# nixie_without_colon.net
KiCad netlist of a schematic drawn in EAGLE
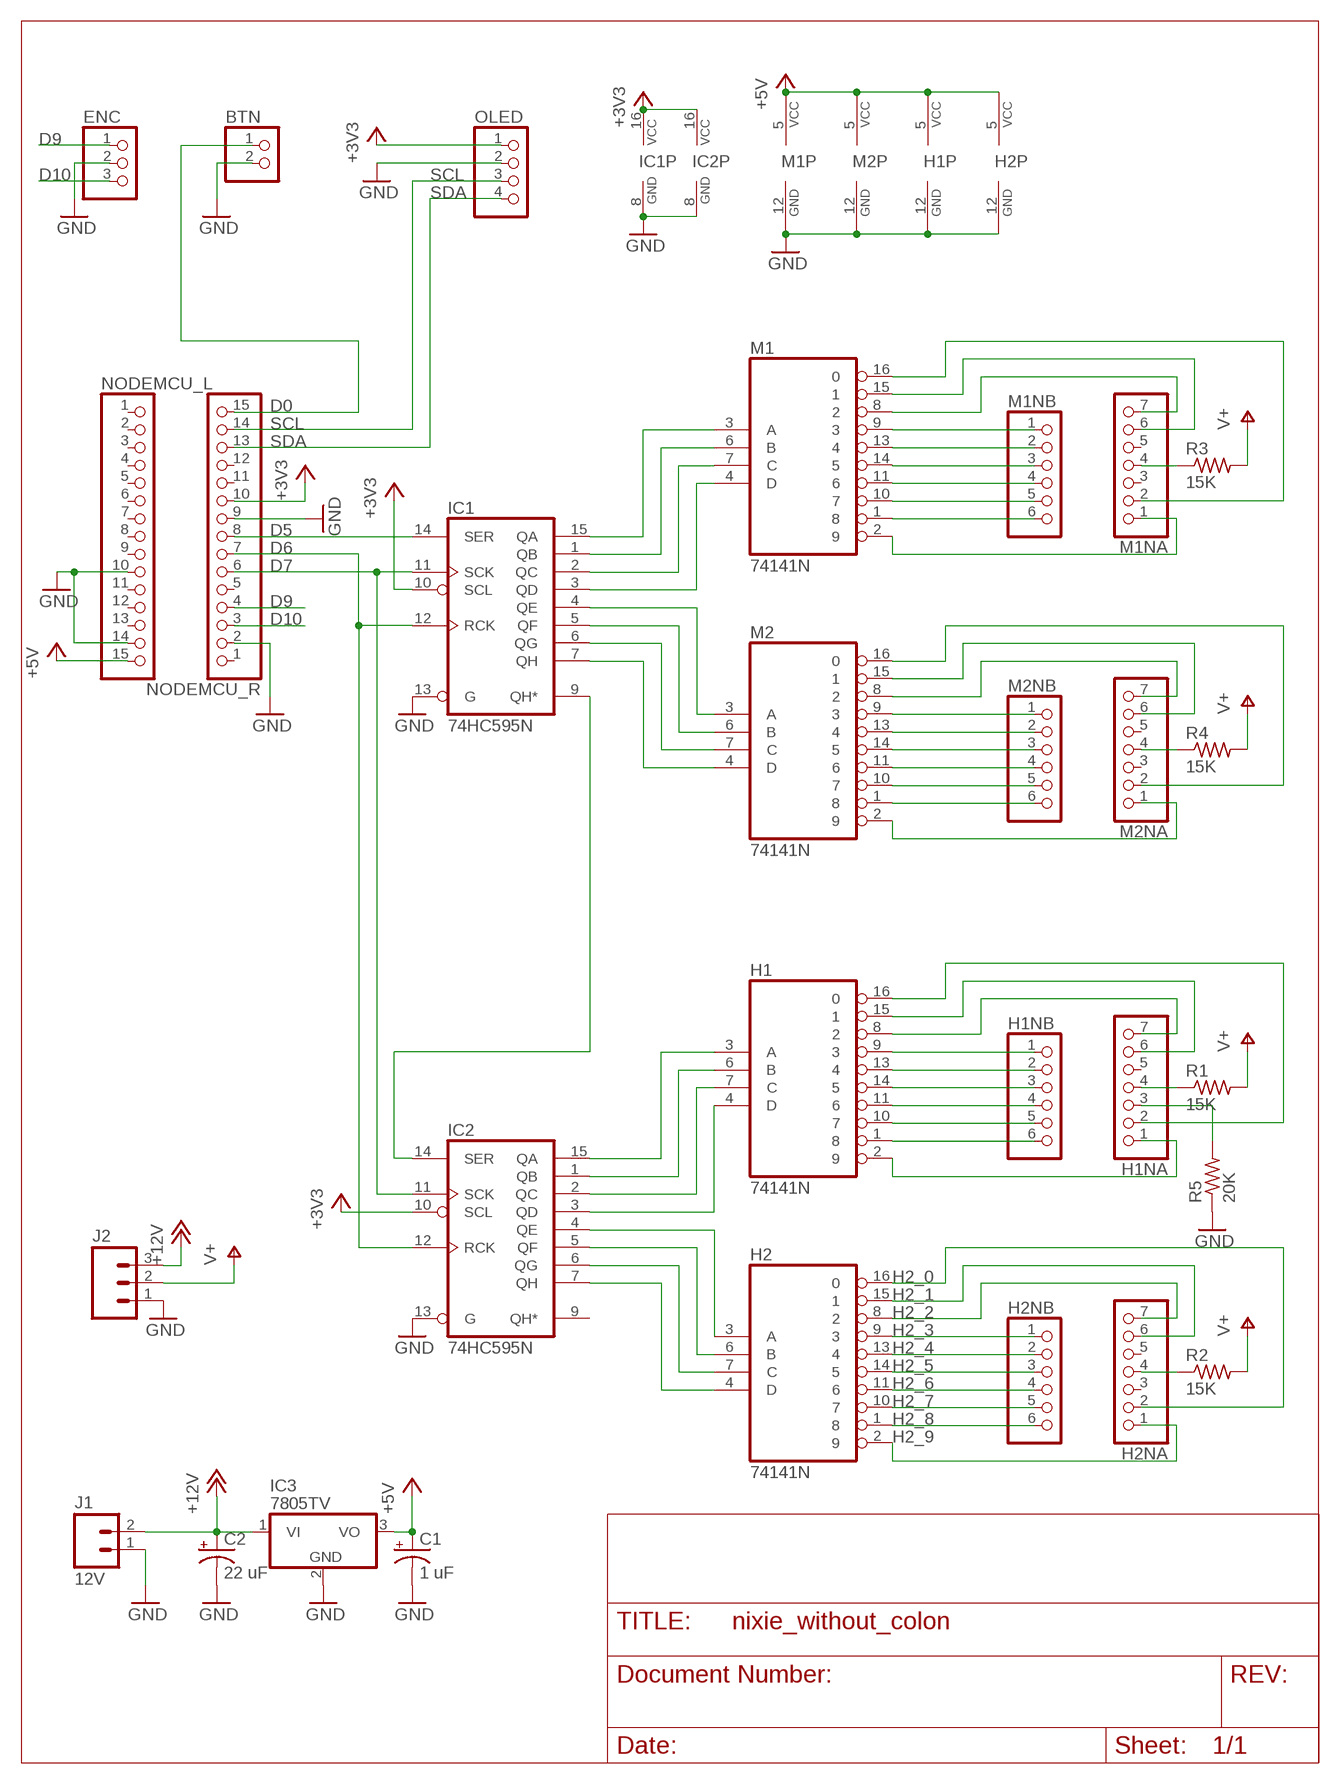
[diagram p0: schematic, sheet 1]

(export (version "E")
  (design (tool "Eeschema 10.0.6"))
  (components
    (comp (ref "BTN")
      (value "PINHD-1X2")
      (footprint "eagle-import:1X02")
      (libsource (lib "eagle-import") (part "PINHD-1X2"))
    )
    (comp (ref "C1")
      (value "1 uF")
      (footprint "eagle-import:TT2D5")
      (libsource (lib "eagle-import") (part "CPOL-USTT2D5"))
    )
    (comp (ref "C2")
      (value "22 uF")
      (footprint "eagle-import:TT2D5")
      (libsource (lib "eagle-import") (part "CPOL-USTT2D5"))
    )
    (comp (ref "ENC")
      (value "PINHD-1X3")
      (footprint "eagle-import:1X03")
      (libsource (lib "eagle-import") (part "PINHD-1X3"))
    )
    (comp (ref "H1")
      (value "74141N")
      (footprint "eagle-import:DIL16")
      (libsource (lib "eagle-import") (part "74141N"))
    )
    (comp (ref "H1NA")
      (value "PINHD-1X7")
      (footprint "eagle-import:1X07")
      (libsource (lib "eagle-import") (part "PINHD-1X7"))
    )
    (comp (ref "H1NB")
      (value "PINHD-1X6")
      (footprint "eagle-import:1X06")
      (libsource (lib "eagle-import") (part "PINHD-1X6"))
    )
    (comp (ref "H2")
      (value "74141N")
      (footprint "eagle-import:DIL16")
      (libsource (lib "eagle-import") (part "74141N"))
    )
    (comp (ref "H2NA")
      (value "PINHD-1X7")
      (footprint "eagle-import:1X07")
      (libsource (lib "eagle-import") (part "PINHD-1X7"))
    )
    (comp (ref "H2NB")
      (value "PINHD-1X6")
      (footprint "eagle-import:1X06")
      (libsource (lib "eagle-import") (part "PINHD-1X6"))
    )
    (comp (ref "IC1")
      (value "74HC595N")
      (footprint "eagle-import:DIL16")
      (libsource (lib "eagle-import") (part "74595NHC"))
    )
    (comp (ref "IC2")
      (value "74HC595N")
      (footprint "eagle-import:DIL16")
      (libsource (lib "eagle-import") (part "74595NHC"))
    )
    (comp (ref "IC3")
      (value "7805TV")
      (footprint "eagle-import:TO220V")
      (libsource (lib "eagle-import") (part "78TV05"))
    )
    (comp (ref "J1")
      (value "12V")
      (footprint "eagle-import:SCREWTERMINAL-5MM-2")
      (libsource (lib "eagle-import") (part "M025MM"))
    )
    (comp (ref "J2")
      (value "M03-SCREW-5MM")
      (footprint "eagle-import:SCREWTERMINAL-5MM-3")
      (libsource (lib "eagle-import") (part "M03-SCREW-5MM"))
    )
    (comp (ref "M1")
      (value "74141N")
      (footprint "eagle-import:DIL16")
      (libsource (lib "eagle-import") (part "74141N"))
    )
    (comp (ref "M1NA")
      (value "PINHD-1X7")
      (footprint "eagle-import:1X07")
      (libsource (lib "eagle-import") (part "PINHD-1X7"))
    )
    (comp (ref "M1NB")
      (value "PINHD-1X6")
      (footprint "eagle-import:1X06")
      (libsource (lib "eagle-import") (part "PINHD-1X6"))
    )
    (comp (ref "M2")
      (value "74141N")
      (footprint "eagle-import:DIL16")
      (libsource (lib "eagle-import") (part "74141N"))
    )
    (comp (ref "M2NA")
      (value "PINHD-1X7")
      (footprint "eagle-import:1X07")
      (libsource (lib "eagle-import") (part "PINHD-1X7"))
    )
    (comp (ref "M2NB")
      (value "PINHD-1X6")
      (footprint "eagle-import:1X06")
      (libsource (lib "eagle-import") (part "PINHD-1X6"))
    )
    (comp (ref "NODEMCU_L")
      (value "PINHD-1X15")
      (footprint "eagle-import:1X15")
      (libsource (lib "eagle-import") (part "PINHD-1X15"))
    )
    (comp (ref "NODEMCU_R")
      (value "PINHD-1X15")
      (footprint "eagle-import:1X15")
      (libsource (lib "eagle-import") (part "PINHD-1X15"))
    )
    (comp (ref "OLED")
      (value "PINHD-1X4")
      (footprint "eagle-import:1X04")
      (libsource (lib "eagle-import") (part "PINHD-1X4"))
    )
    (comp (ref "R1")
      (value "15K")
      (footprint "eagle-import:0207_10")
      (libsource (lib "eagle-import") (part "R-US_0207/10"))
    )
    (comp (ref "R2")
      (value "15K")
      (footprint "eagle-import:0207_10")
      (libsource (lib "eagle-import") (part "R-US_0207/10"))
    )
    (comp (ref "R3")
      (value "15K")
      (footprint "eagle-import:0207_10")
      (libsource (lib "eagle-import") (part "R-US_0207/10"))
    )
    (comp (ref "R4")
      (value "15K")
      (footprint "eagle-import:0207_10")
      (libsource (lib "eagle-import") (part "R-US_0207/10"))
    )
    (comp (ref "R5")
      (value "20K")
      (footprint "eagle-import:0207_10")
      (libsource (lib "eagle-import") (part "R-US_0207/10"))
    )
  )
  (nets
    (net (code "1") (name "+3V3") (class "Default")
      (node (ref "IC1") (pin "10") (pinfunction "SCL_10") (pintype "input"))
      (node (ref "IC1") (pin "16") (pinfunction "VCC_16") (pintype "power_in"))
      (node (ref "IC2") (pin "10") (pinfunction "SCL_10") (pintype "input"))
      (node (ref "IC2") (pin "16") (pinfunction "VCC_16") (pintype "power_in"))
      (node (ref "NODEMCU_R") (pin "10") (pinfunction "10_10") (pintype "passive"))
      (node (ref "OLED") (pin "1") (pinfunction "1_1") (pintype "passive"))
    )
    (net (code "2") (name "+5V") (class "Default")
      (node (ref "C1") (pin "+") (pinfunction "+_+") (pintype "passive"))
      (node (ref "H1") (pin "5") (pinfunction "VCC_5") (pintype "power_in"))
      (node (ref "H2") (pin "5") (pinfunction "VCC_5") (pintype "power_in"))
      (node (ref "IC3") (pin "3") (pinfunction "VO_3") (pintype "passive"))
      (node (ref "M1") (pin "5") (pinfunction "VCC_5") (pintype "power_in"))
      (node (ref "M2") (pin "5") (pinfunction "VCC_5") (pintype "power_in"))
      (node (ref "NODEMCU_L") (pin "15") (pinfunction "15_15") (pintype "passive"))
    )
    (net (code "3") (name "+12V") (class "Default")
      (node (ref "C2") (pin "+") (pinfunction "+_+") (pintype "passive"))
      (node (ref "IC3") (pin "1") (pinfunction "VI_1") (pintype "input"))
      (node (ref "J1") (pin "2") (pinfunction "2_2") (pintype "passive"))
      (node (ref "J2") (pin "3") (pinfunction "3_3") (pintype "passive"))
    )
    (net (code "4") (name "/D0") (class "Default")
      (node (ref "BTN") (pin "1") (pinfunction "1_1") (pintype "passive"))
      (node (ref "NODEMCU_R") (pin "15") (pinfunction "15_15") (pintype "passive"))
    )
    (net (code "5") (name "/D5") (class "Default")
      (node (ref "IC1") (pin "14") (pinfunction "SER_14") (pintype "input"))
      (node (ref "NODEMCU_R") (pin "8") (pinfunction "8_8") (pintype "passive"))
    )
    (net (code "6") (name "/D6") (class "Default")
      (node (ref "IC1") (pin "12") (pinfunction "RCK_12") (pintype "input"))
      (node (ref "IC2") (pin "12") (pinfunction "RCK_12") (pintype "input"))
      (node (ref "NODEMCU_R") (pin "7") (pinfunction "7_7") (pintype "passive"))
    )
    (net (code "7") (name "/D7") (class "Default")
      (node (ref "IC1") (pin "11") (pinfunction "SCK_11") (pintype "input"))
      (node (ref "IC2") (pin "11") (pinfunction "SCK_11") (pintype "input"))
      (node (ref "NODEMCU_R") (pin "6") (pinfunction "6_6") (pintype "passive"))
    )
    (net (code "8") (name "/D9") (class "Default")
      (node (ref "ENC") (pin "1") (pinfunction "1_1") (pintype "passive"))
      (node (ref "NODEMCU_R") (pin "4") (pinfunction "4_4") (pintype "passive"))
    )
    (net (code "9") (name "/D10") (class "Default")
      (node (ref "ENC") (pin "3") (pinfunction "3_3") (pintype "passive"))
      (node (ref "NODEMCU_R") (pin "3") (pinfunction "3_3") (pintype "passive"))
    )
    (net (code "10") (name "/H2_0") (class "Default")
      (node (ref "H2") (pin "16") (pinfunction "0_16") (pintype "open_collector"))
      (node (ref "H2NA") (pin "2") (pinfunction "2_2") (pintype "passive"))
    )
    (net (code "11") (name "/H2_1") (class "Default")
      (node (ref "H2") (pin "15") (pinfunction "1_15") (pintype "open_collector"))
      (node (ref "H2NA") (pin "6") (pinfunction "6_6") (pintype "passive"))
    )
    (net (code "12") (name "/H2_2") (class "Default")
      (node (ref "H2") (pin "8") (pinfunction "2_8") (pintype "open_collector"))
      (node (ref "H2NA") (pin "7") (pinfunction "7_7") (pintype "passive"))
    )
    (net (code "13") (name "/H2_3") (class "Default")
      (node (ref "H2") (pin "9") (pinfunction "3_9") (pintype "open_collector"))
      (node (ref "H2NB") (pin "1") (pinfunction "1_1") (pintype "passive"))
    )
    (net (code "14") (name "/H2_4") (class "Default")
      (node (ref "H2") (pin "13") (pinfunction "4_13") (pintype "open_collector"))
      (node (ref "H2NB") (pin "2") (pinfunction "2_2") (pintype "passive"))
    )
    (net (code "15") (name "/H2_5") (class "Default")
      (node (ref "H2") (pin "14") (pinfunction "5_14") (pintype "open_collector"))
      (node (ref "H2NB") (pin "3") (pinfunction "3_3") (pintype "passive"))
    )
    (net (code "16") (name "/H2_6") (class "Default")
      (node (ref "H2") (pin "11") (pinfunction "6_11") (pintype "open_collector"))
      (node (ref "H2NB") (pin "4") (pinfunction "4_4") (pintype "passive"))
    )
    (net (code "17") (name "/H2_7") (class "Default")
      (node (ref "H2") (pin "10") (pinfunction "7_10") (pintype "open_collector"))
      (node (ref "H2NB") (pin "5") (pinfunction "5_5") (pintype "passive"))
    )
    (net (code "18") (name "/H2_8") (class "Default")
      (node (ref "H2") (pin "1") (pinfunction "8_1") (pintype "open_collector"))
      (node (ref "H2NB") (pin "6") (pinfunction "6_6") (pintype "passive"))
    )
    (net (code "19") (name "/H2_9") (class "Default")
      (node (ref "H2") (pin "2") (pinfunction "9_2") (pintype "open_collector"))
      (node (ref "H2NA") (pin "1") (pinfunction "1_1") (pintype "passive"))
    )
    (net (code "20") (name "/SCL") (class "Default")
      (node (ref "NODEMCU_R") (pin "14") (pinfunction "14_14") (pintype "passive"))
      (node (ref "OLED") (pin "3") (pinfunction "3_3") (pintype "passive"))
    )
    (net (code "21") (name "/SDA") (class "Default")
      (node (ref "NODEMCU_R") (pin "13") (pinfunction "13_13") (pintype "passive"))
      (node (ref "OLED") (pin "4") (pinfunction "4_4") (pintype "passive"))
    )
    (net (code "22") (name "GND") (class "Default")
      (node (ref "BTN") (pin "2") (pinfunction "2_2") (pintype "passive"))
      (node (ref "C1") (pin "-") (pinfunction "-_-") (pintype "passive"))
      (node (ref "C2") (pin "-") (pinfunction "-_-") (pintype "passive"))
      (node (ref "ENC") (pin "2") (pinfunction "2_2") (pintype "passive"))
      (node (ref "H1") (pin "12") (pinfunction "GND_12") (pintype "power_in"))
      (node (ref "H2") (pin "12") (pinfunction "GND_12") (pintype "power_in"))
      (node (ref "IC1") (pin "13") (pinfunction "G_13") (pintype "input"))
      (node (ref "IC1") (pin "8") (pinfunction "GND_8") (pintype "power_in"))
      (node (ref "IC2") (pin "13") (pinfunction "G_13") (pintype "input"))
      (node (ref "IC2") (pin "8") (pinfunction "GND_8") (pintype "power_in"))
      (node (ref "IC3") (pin "2") (pinfunction "GND_2") (pintype "passive"))
      (node (ref "J1") (pin "1") (pinfunction "1_1") (pintype "passive"))
      (node (ref "J2") (pin "1") (pinfunction "1_1") (pintype "passive"))
      (node (ref "M1") (pin "12") (pinfunction "GND_12") (pintype "power_in"))
      (node (ref "M2") (pin "12") (pinfunction "GND_12") (pintype "power_in"))
      (node (ref "NODEMCU_L") (pin "10") (pinfunction "10_10") (pintype "passive"))
      (node (ref "NODEMCU_L") (pin "14") (pinfunction "14_14") (pintype "passive"))
      (node (ref "NODEMCU_R") (pin "2") (pinfunction "2_2") (pintype "passive"))
      (node (ref "NODEMCU_R") (pin "9") (pinfunction "9_9") (pintype "passive"))
      (node (ref "OLED") (pin "2") (pinfunction "2_2") (pintype "passive"))
      (node (ref "R5") (pin "1") (pinfunction "1_1") (pintype "passive"))
    )
    (net (code "23") (name "Net-(H1A-0)") (class "Default")
      (node (ref "H1") (pin "16") (pinfunction "0_16") (pintype "open_collector"))
      (node (ref "H1NA") (pin "2") (pinfunction "2_2") (pintype "passive"))
    )
    (net (code "24") (name "Net-(H1A-1)") (class "Default")
      (node (ref "H1") (pin "15") (pinfunction "1_15") (pintype "open_collector"))
      (node (ref "H1NA") (pin "6") (pinfunction "6_6") (pintype "passive"))
    )
    (net (code "25") (name "Net-(H1A-2)") (class "Default")
      (node (ref "H1") (pin "8") (pinfunction "2_8") (pintype "open_collector"))
      (node (ref "H1NA") (pin "7") (pinfunction "7_7") (pintype "passive"))
    )
    (net (code "26") (name "Net-(H1A-3)") (class "Default")
      (node (ref "H1") (pin "9") (pinfunction "3_9") (pintype "open_collector"))
      (node (ref "H1NB") (pin "1") (pinfunction "1_1") (pintype "passive"))
    )
    (net (code "27") (name "Net-(H1A-4)") (class "Default")
      (node (ref "H1") (pin "13") (pinfunction "4_13") (pintype "open_collector"))
      (node (ref "H1NB") (pin "2") (pinfunction "2_2") (pintype "passive"))
    )
    (net (code "28") (name "Net-(H1A-5)") (class "Default")
      (node (ref "H1") (pin "14") (pinfunction "5_14") (pintype "open_collector"))
      (node (ref "H1NB") (pin "3") (pinfunction "3_3") (pintype "passive"))
    )
    (net (code "29") (name "Net-(H1A-6)") (class "Default")
      (node (ref "H1") (pin "11") (pinfunction "6_11") (pintype "open_collector"))
      (node (ref "H1NB") (pin "4") (pinfunction "4_4") (pintype "passive"))
    )
    (net (code "30") (name "Net-(H1A-7)") (class "Default")
      (node (ref "H1") (pin "10") (pinfunction "7_10") (pintype "open_collector"))
      (node (ref "H1NB") (pin "5") (pinfunction "5_5") (pintype "passive"))
    )
    (net (code "31") (name "Net-(H1A-8)") (class "Default")
      (node (ref "H1") (pin "1") (pinfunction "8_1") (pintype "open_collector"))
      (node (ref "H1NB") (pin "6") (pinfunction "6_6") (pintype "passive"))
    )
    (net (code "32") (name "Net-(H1A-9)") (class "Default")
      (node (ref "H1") (pin "2") (pinfunction "9_2") (pintype "open_collector"))
      (node (ref "H1NA") (pin "1") (pinfunction "1_1") (pintype "passive"))
    )
    (net (code "33") (name "Net-(H1A-A)") (class "Default")
      (node (ref "H1") (pin "3") (pinfunction "A_3") (pintype "input"))
      (node (ref "IC2") (pin "15") (pinfunction "QA_15") (pintype "tri_state"))
    )
    (net (code "34") (name "Net-(H1A-B)") (class "Default")
      (node (ref "H1") (pin "6") (pinfunction "B_6") (pintype "input"))
      (node (ref "IC2") (pin "1") (pinfunction "QB_1") (pintype "tri_state"))
    )
    (net (code "35") (name "Net-(H1A-C)") (class "Default")
      (node (ref "H1") (pin "7") (pinfunction "C_7") (pintype "input"))
      (node (ref "IC2") (pin "2") (pinfunction "QC_2") (pintype "tri_state"))
    )
    (net (code "36") (name "Net-(H1A-D)") (class "Default")
      (node (ref "H1") (pin "4") (pinfunction "D_4") (pintype "input"))
      (node (ref "IC2") (pin "3") (pinfunction "QD_3") (pintype "tri_state"))
    )
    (net (code "37") (name "Net-(H1NA-Pad3)") (class "Default")
      (node (ref "H1NA") (pin "3") (pinfunction "3_3") (pintype "passive"))
      (node (ref "R5") (pin "2") (pinfunction "2_2") (pintype "passive"))
    )
    (net (code "38") (name "Net-(H1NA-Pad4)") (class "Default")
      (node (ref "H1NA") (pin "4") (pinfunction "4_4") (pintype "passive"))
      (node (ref "R1") (pin "1") (pinfunction "1_1") (pintype "passive"))
    )
    (net (code "39") (name "Net-(H2A-A)") (class "Default")
      (node (ref "H2") (pin "3") (pinfunction "A_3") (pintype "input"))
      (node (ref "IC2") (pin "4") (pinfunction "QE_4") (pintype "tri_state"))
    )
    (net (code "40") (name "Net-(H2A-B)") (class "Default")
      (node (ref "H2") (pin "6") (pinfunction "B_6") (pintype "input"))
      (node (ref "IC2") (pin "5") (pinfunction "QF_5") (pintype "tri_state"))
    )
    (net (code "41") (name "Net-(H2A-C)") (class "Default")
      (node (ref "H2") (pin "7") (pinfunction "C_7") (pintype "input"))
      (node (ref "IC2") (pin "6") (pinfunction "QG_6") (pintype "tri_state"))
    )
    (net (code "42") (name "Net-(H2A-D)") (class "Default")
      (node (ref "H2") (pin "4") (pinfunction "D_4") (pintype "input"))
      (node (ref "IC2") (pin "7") (pinfunction "QH_7") (pintype "tri_state"))
    )
    (net (code "43") (name "Net-(H2NA-Pad4)") (class "Default")
      (node (ref "H2NA") (pin "4") (pinfunction "4_4") (pintype "passive"))
      (node (ref "R2") (pin "1") (pinfunction "1_1") (pintype "passive"))
    )
    (net (code "44") (name "Net-(IC1A-QA)") (class "Default")
      (node (ref "IC1") (pin "15") (pinfunction "QA_15") (pintype "tri_state"))
      (node (ref "M1") (pin "3") (pinfunction "A_3") (pintype "input"))
    )
    (net (code "45") (name "Net-(IC1A-QB)") (class "Default")
      (node (ref "IC1") (pin "1") (pinfunction "QB_1") (pintype "tri_state"))
      (node (ref "M1") (pin "6") (pinfunction "B_6") (pintype "input"))
    )
    (net (code "46") (name "Net-(IC1A-QC)") (class "Default")
      (node (ref "IC1") (pin "2") (pinfunction "QC_2") (pintype "tri_state"))
      (node (ref "M1") (pin "7") (pinfunction "C_7") (pintype "input"))
    )
    (net (code "47") (name "Net-(IC1A-QD)") (class "Default")
      (node (ref "IC1") (pin "3") (pinfunction "QD_3") (pintype "tri_state"))
      (node (ref "M1") (pin "4") (pinfunction "D_4") (pintype "input"))
    )
    (net (code "48") (name "Net-(IC1A-QE)") (class "Default")
      (node (ref "IC1") (pin "4") (pinfunction "QE_4") (pintype "tri_state"))
      (node (ref "M2") (pin "3") (pinfunction "A_3") (pintype "input"))
    )
    (net (code "49") (name "Net-(IC1A-QF)") (class "Default")
      (node (ref "IC1") (pin "5") (pinfunction "QF_5") (pintype "tri_state"))
      (node (ref "M2") (pin "6") (pinfunction "B_6") (pintype "input"))
    )
    (net (code "50") (name "Net-(IC1A-QG)") (class "Default")
      (node (ref "IC1") (pin "6") (pinfunction "QG_6") (pintype "tri_state"))
      (node (ref "M2") (pin "7") (pinfunction "C_7") (pintype "input"))
    )
    (net (code "51") (name "Net-(IC1A-QH)") (class "Default")
      (node (ref "IC1") (pin "7") (pinfunction "QH_7") (pintype "tri_state"))
      (node (ref "M2") (pin "4") (pinfunction "D_4") (pintype "input"))
    )
    (net (code "52") (name "Net-(IC1A-QH*)") (class "Default")
      (node (ref "IC1") (pin "9") (pinfunction "QH*_9") (pintype "tri_state"))
      (node (ref "IC2") (pin "14") (pinfunction "SER_14") (pintype "input"))
    )
    (net (code "53") (name "Net-(M1A-0)") (class "Default")
      (node (ref "M1") (pin "16") (pinfunction "0_16") (pintype "open_collector"))
      (node (ref "M1NA") (pin "2") (pinfunction "2_2") (pintype "passive"))
    )
    (net (code "54") (name "Net-(M1A-1)") (class "Default")
      (node (ref "M1") (pin "15") (pinfunction "1_15") (pintype "open_collector"))
      (node (ref "M1NA") (pin "6") (pinfunction "6_6") (pintype "passive"))
    )
    (net (code "55") (name "Net-(M1A-2)") (class "Default")
      (node (ref "M1") (pin "8") (pinfunction "2_8") (pintype "open_collector"))
      (node (ref "M1NA") (pin "7") (pinfunction "7_7") (pintype "passive"))
    )
    (net (code "56") (name "Net-(M1A-3)") (class "Default")
      (node (ref "M1") (pin "9") (pinfunction "3_9") (pintype "open_collector"))
      (node (ref "M1NB") (pin "1") (pinfunction "1_1") (pintype "passive"))
    )
    (net (code "57") (name "Net-(M1A-4)") (class "Default")
      (node (ref "M1") (pin "13") (pinfunction "4_13") (pintype "open_collector"))
      (node (ref "M1NB") (pin "2") (pinfunction "2_2") (pintype "passive"))
    )
    (net (code "58") (name "Net-(M1A-5)") (class "Default")
      (node (ref "M1") (pin "14") (pinfunction "5_14") (pintype "open_collector"))
      (node (ref "M1NB") (pin "3") (pinfunction "3_3") (pintype "passive"))
    )
    (net (code "59") (name "Net-(M1A-6)") (class "Default")
      (node (ref "M1") (pin "11") (pinfunction "6_11") (pintype "open_collector"))
      (node (ref "M1NB") (pin "4") (pinfunction "4_4") (pintype "passive"))
    )
    (net (code "60") (name "Net-(M1A-7)") (class "Default")
      (node (ref "M1") (pin "10") (pinfunction "7_10") (pintype "open_collector"))
      (node (ref "M1NB") (pin "5") (pinfunction "5_5") (pintype "passive"))
    )
    (net (code "61") (name "Net-(M1A-8)") (class "Default")
      (node (ref "M1") (pin "1") (pinfunction "8_1") (pintype "open_collector"))
      (node (ref "M1NB") (pin "6") (pinfunction "6_6") (pintype "passive"))
    )
    (net (code "62") (name "Net-(M1A-9)") (class "Default")
      (node (ref "M1") (pin "2") (pinfunction "9_2") (pintype "open_collector"))
      (node (ref "M1NA") (pin "1") (pinfunction "1_1") (pintype "passive"))
    )
    (net (code "63") (name "Net-(M1NA-Pad4)") (class "Default")
      (node (ref "M1NA") (pin "4") (pinfunction "4_4") (pintype "passive"))
      (node (ref "R3") (pin "1") (pinfunction "1_1") (pintype "passive"))
    )
    (net (code "64") (name "Net-(M2A-0)") (class "Default")
      (node (ref "M2") (pin "16") (pinfunction "0_16") (pintype "open_collector"))
      (node (ref "M2NA") (pin "2") (pinfunction "2_2") (pintype "passive"))
    )
    (net (code "65") (name "Net-(M2A-1)") (class "Default")
      (node (ref "M2") (pin "15") (pinfunction "1_15") (pintype "open_collector"))
      (node (ref "M2NA") (pin "6") (pinfunction "6_6") (pintype "passive"))
    )
    (net (code "66") (name "Net-(M2A-2)") (class "Default")
      (node (ref "M2") (pin "8") (pinfunction "2_8") (pintype "open_collector"))
      (node (ref "M2NA") (pin "7") (pinfunction "7_7") (pintype "passive"))
    )
    (net (code "67") (name "Net-(M2A-3)") (class "Default")
      (node (ref "M2") (pin "9") (pinfunction "3_9") (pintype "open_collector"))
      (node (ref "M2NB") (pin "1") (pinfunction "1_1") (pintype "passive"))
    )
    (net (code "68") (name "Net-(M2A-4)") (class "Default")
      (node (ref "M2") (pin "13") (pinfunction "4_13") (pintype "open_collector"))
      (node (ref "M2NB") (pin "2") (pinfunction "2_2") (pintype "passive"))
    )
    (net (code "69") (name "Net-(M2A-5)") (class "Default")
      (node (ref "M2") (pin "14") (pinfunction "5_14") (pintype "open_collector"))
      (node (ref "M2NB") (pin "3") (pinfunction "3_3") (pintype "passive"))
    )
    (net (code "70") (name "Net-(M2A-6)") (class "Default")
      (node (ref "M2") (pin "11") (pinfunction "6_11") (pintype "open_collector"))
      (node (ref "M2NB") (pin "4") (pinfunction "4_4") (pintype "passive"))
    )
    (net (code "71") (name "Net-(M2A-7)") (class "Default")
      (node (ref "M2") (pin "10") (pinfunction "7_10") (pintype "open_collector"))
      (node (ref "M2NB") (pin "5") (pinfunction "5_5") (pintype "passive"))
    )
    (net (code "72") (name "Net-(M2A-8)") (class "Default")
      (node (ref "M2") (pin "1") (pinfunction "8_1") (pintype "open_collector"))
      (node (ref "M2NB") (pin "6") (pinfunction "6_6") (pintype "passive"))
    )
    (net (code "73") (name "Net-(M2A-9)") (class "Default")
      (node (ref "M2") (pin "2") (pinfunction "9_2") (pintype "open_collector"))
      (node (ref "M2NA") (pin "1") (pinfunction "1_1") (pintype "passive"))
    )
    (net (code "74") (name "Net-(M2NA-Pad4)") (class "Default")
      (node (ref "M2NA") (pin "4") (pinfunction "4_4") (pintype "passive"))
      (node (ref "R4") (pin "1") (pinfunction "1_1") (pintype "passive"))
    )
    (net (code "75") (name "V+") (class "Default")
      (node (ref "J2") (pin "2") (pinfunction "2_2") (pintype "passive"))
      (node (ref "R1") (pin "2") (pinfunction "2_2") (pintype "passive"))
      (node (ref "R2") (pin "2") (pinfunction "2_2") (pintype "passive"))
      (node (ref "R3") (pin "2") (pinfunction "2_2") (pintype "passive"))
      (node (ref "R4") (pin "2") (pinfunction "2_2") (pintype "passive"))
    )
    (net (code "76") (name "unconnected-(H1NA-Pad5)") (class "Default")
      (node (ref "H1NA") (pin "5") (pinfunction "5_5") (pintype "passive"))
    )
    (net (code "77") (name "unconnected-(H2NA-Pad3)") (class "Default")
      (node (ref "H2NA") (pin "3") (pinfunction "3_3") (pintype "passive"))
    )
    (net (code "78") (name "unconnected-(H2NA-Pad5)") (class "Default")
      (node (ref "H2NA") (pin "5") (pinfunction "5_5") (pintype "passive"))
    )
    (net (code "79") (name "unconnected-(IC2A-QH*-Pad9)") (class "Default")
      (node (ref "IC2") (pin "9") (pinfunction "QH*_9") (pintype "tri_state"))
    )
    (net (code "80") (name "unconnected-(M1NA-Pad3)") (class "Default")
      (node (ref "M1NA") (pin "3") (pinfunction "3_3") (pintype "passive"))
    )
    (net (code "81") (name "unconnected-(M1NA-Pad5)") (class "Default")
      (node (ref "M1NA") (pin "5") (pinfunction "5_5") (pintype "passive"))
    )
    (net (code "82") (name "unconnected-(M2NA-Pad3)") (class "Default")
      (node (ref "M2NA") (pin "3") (pinfunction "3_3") (pintype "passive"))
    )
    (net (code "83") (name "unconnected-(M2NA-Pad5)") (class "Default")
      (node (ref "M2NA") (pin "5") (pinfunction "5_5") (pintype "passive"))
    )
    (net (code "84") (name "unconnected-(NODEMCU_L-Pad1)") (class "Default")
      (node (ref "NODEMCU_L") (pin "1") (pinfunction "1_1") (pintype "passive"))
    )
    (net (code "85") (name "unconnected-(NODEMCU_L-Pad2)") (class "Default")
      (node (ref "NODEMCU_L") (pin "2") (pinfunction "2_2") (pintype "passive"))
    )
    (net (code "86") (name "unconnected-(NODEMCU_L-Pad3)") (class "Default")
      (node (ref "NODEMCU_L") (pin "3") (pinfunction "3_3") (pintype "passive"))
    )
    (net (code "87") (name "unconnected-(NODEMCU_L-Pad4)") (class "Default")
      (node (ref "NODEMCU_L") (pin "4") (pinfunction "4_4") (pintype "passive"))
    )
    (net (code "88") (name "unconnected-(NODEMCU_L-Pad5)") (class "Default")
      (node (ref "NODEMCU_L") (pin "5") (pinfunction "5_5") (pintype "passive"))
    )
    (net (code "89") (name "unconnected-(NODEMCU_L-Pad6)") (class "Default")
      (node (ref "NODEMCU_L") (pin "6") (pinfunction "6_6") (pintype "passive"))
    )
    (net (code "90") (name "unconnected-(NODEMCU_L-Pad7)") (class "Default")
      (node (ref "NODEMCU_L") (pin "7") (pinfunction "7_7") (pintype "passive"))
    )
    (net (code "91") (name "unconnected-(NODEMCU_L-Pad8)") (class "Default")
      (node (ref "NODEMCU_L") (pin "8") (pinfunction "8_8") (pintype "passive"))
    )
    (net (code "92") (name "unconnected-(NODEMCU_L-Pad9)") (class "Default")
      (node (ref "NODEMCU_L") (pin "9") (pinfunction "9_9") (pintype "passive"))
    )
    (net (code "93") (name "unconnected-(NODEMCU_L-Pad11)") (class "Default")
      (node (ref "NODEMCU_L") (pin "11") (pinfunction "11_11") (pintype "passive"))
    )
    (net (code "94") (name "unconnected-(NODEMCU_L-Pad12)") (class "Default")
      (node (ref "NODEMCU_L") (pin "12") (pinfunction "12_12") (pintype "passive"))
    )
    (net (code "95") (name "unconnected-(NODEMCU_L-Pad13)") (class "Default")
      (node (ref "NODEMCU_L") (pin "13") (pinfunction "13_13") (pintype "passive"))
    )
    (net (code "96") (name "unconnected-(NODEMCU_R-Pad1)") (class "Default")
      (node (ref "NODEMCU_R") (pin "1") (pinfunction "1_1") (pintype "passive"))
    )
    (net (code "97") (name "unconnected-(NODEMCU_R-Pad5)") (class "Default")
      (node (ref "NODEMCU_R") (pin "5") (pinfunction "5_5") (pintype "passive"))
    )
    (net (code "98") (name "unconnected-(NODEMCU_R-Pad11)") (class "Default")
      (node (ref "NODEMCU_R") (pin "11") (pinfunction "11_11") (pintype "passive"))
    )
    (net (code "99") (name "unconnected-(NODEMCU_R-Pad12)") (class "Default")
      (node (ref "NODEMCU_R") (pin "12") (pinfunction "12_12") (pintype "passive"))
    )
  )
)
